# Ad8232_placa_C_malha.net
KiCad netlist of a schematic drawn in EAGLE
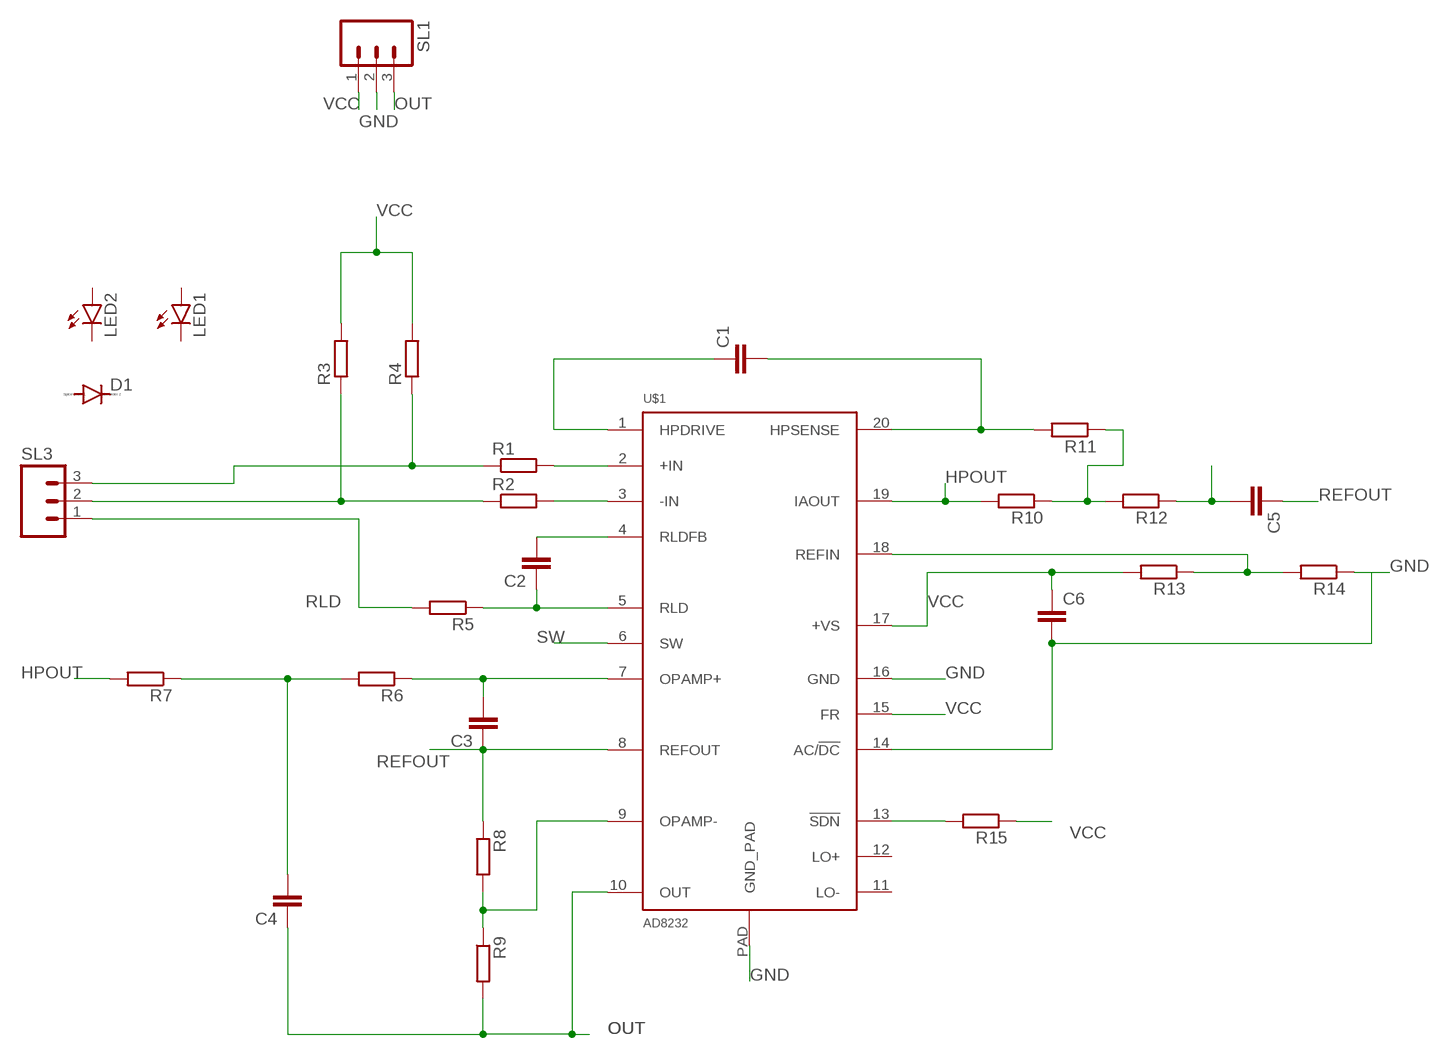
[diagram p0: schematic, sheet 1]

(export (version "E")
  (design (tool "Eeschema 10.0.6"))
  (components
    (comp (ref "C1")
      (value "C-EUC0805")
      (footprint "eagle-import:C0805")
      (libsource (lib "eagle-import") (part "C-EUC0805"))
    )
    (comp (ref "C2")
      (value "C-EUC0805")
      (footprint "eagle-import:C0805")
      (libsource (lib "eagle-import") (part "C-EUC0805"))
    )
    (comp (ref "C3")
      (value "C-EUC0805")
      (footprint "eagle-import:C0805")
      (libsource (lib "eagle-import") (part "C-EUC0805"))
    )
    (comp (ref "C4")
      (value "C-EUC0805")
      (footprint "eagle-import:C0805")
      (libsource (lib "eagle-import") (part "C-EUC0805"))
    )
    (comp (ref "C5")
      (value "C-EUC0805")
      (footprint "eagle-import:C0805")
      (libsource (lib "eagle-import") (part "C-EUC0805"))
    )
    (comp (ref "C6")
      (value "C-EUC0805")
      (footprint "eagle-import:C0805")
      (libsource (lib "eagle-import") (part "C-EUC0805"))
    )
    (comp (ref "D1")
      (value "DIODE-MINIMELF")
      (footprint "eagle-import:MINIMELF")
      (libsource (lib "eagle-import") (part "DIODE-MINIMELF"))
    )
    (comp (ref "LED1")
      (value "LEDCHIPLED_0603")
      (footprint "eagle-import:CHIPLED_0603")
      (libsource (lib "eagle-import") (part "LEDCHIPLED_0603"))
    )
    (comp (ref "LED2")
      (value "LEDCHIPLED_0603")
      (footprint "eagle-import:CHIPLED_0603")
      (libsource (lib "eagle-import") (part "LEDCHIPLED_0603"))
    )
    (comp (ref "R1")
      (value "R-EU_R0805")
      (footprint "eagle-import:R0805")
      (libsource (lib "eagle-import") (part "R-EU_R0805"))
    )
    (comp (ref "R2")
      (value "R-EU_R0805")
      (footprint "eagle-import:R0805")
      (libsource (lib "eagle-import") (part "R-EU_R0805"))
    )
    (comp (ref "R3")
      (value "R-EU_R0805")
      (footprint "eagle-import:R0805")
      (libsource (lib "eagle-import") (part "R-EU_R0805"))
    )
    (comp (ref "R4")
      (value "R-EU_R0805")
      (footprint "eagle-import:R0805")
      (libsource (lib "eagle-import") (part "R-EU_R0805"))
    )
    (comp (ref "R5")
      (value "R-EU_R0805")
      (footprint "eagle-import:R0805")
      (libsource (lib "eagle-import") (part "R-EU_R0805"))
    )
    (comp (ref "R6")
      (value "R-EU_R0805")
      (footprint "eagle-import:R0805")
      (libsource (lib "eagle-import") (part "R-EU_R0805"))
    )
    (comp (ref "R7")
      (value "R-EU_R0805")
      (footprint "eagle-import:R0805")
      (libsource (lib "eagle-import") (part "R-EU_R0805"))
    )
    (comp (ref "R8")
      (value "R-EU_R0805")
      (footprint "eagle-import:R0805")
      (libsource (lib "eagle-import") (part "R-EU_R0805"))
    )
    (comp (ref "R9")
      (value "R-EU_R0805")
      (footprint "eagle-import:R0805")
      (libsource (lib "eagle-import") (part "R-EU_R0805"))
    )
    (comp (ref "R10")
      (value "R-EU_R0805")
      (footprint "eagle-import:R0805")
      (libsource (lib "eagle-import") (part "R-EU_R0805"))
    )
    (comp (ref "R11")
      (value "R-EU_R0805")
      (footprint "eagle-import:R0805")
      (libsource (lib "eagle-import") (part "R-EU_R0805"))
    )
    (comp (ref "R12")
      (value "R-EU_R0805")
      (footprint "eagle-import:R0805")
      (libsource (lib "eagle-import") (part "R-EU_R0805"))
    )
    (comp (ref "R13")
      (value "R-EU_R0805")
      (footprint "eagle-import:R0805")
      (libsource (lib "eagle-import") (part "R-EU_R0805"))
    )
    (comp (ref "R14")
      (value "R-EU_R0805")
      (footprint "eagle-import:R0805")
      (libsource (lib "eagle-import") (part "R-EU_R0805"))
    )
    (comp (ref "R15")
      (value "R-EU_R0805")
      (footprint "eagle-import:R0805")
      (libsource (lib "eagle-import") (part "R-EU_R0805"))
    )
    (comp (ref "SL1")
      (value "M03")
      (footprint "eagle-import:03P")
      (libsource (lib "eagle-import") (part "M03"))
    )
    (comp (ref "SL3")
      (value "M03")
      (footprint "eagle-import:03P")
      (libsource (lib "eagle-import") (part "M03"))
    )
    (comp (ref "U$1")
      (value "AD8232")
      (footprint "eagle-import:LFCSP_20")
      (fields (field (name "MF") "Analog Devices"))
      (libsource (lib "eagle-import") (part "AD8232"))
    )
  )
  (nets
    (net (code "1") (name "/GND") (class "Default")
      (node (ref "C6") (pin "2") (pinfunction "2_2") (pintype "passive"))
      (node (ref "R14") (pin "1") (pinfunction "1_1") (pintype "passive"))
      (node (ref "SL1") (pin "2") (pinfunction "2_2") (pintype "passive"))
      (node (ref "U$1") (pin "14") (pinfunction "AC/~{DC}_14") (pintype "bidirectional"))
      (node (ref "U$1") (pin "16") (pinfunction "GND_16") (pintype "bidirectional"))
      (node (ref "U$1") (pin "PAD") (pinfunction "GND_PAD_PAD") (pintype "bidirectional"))
    )
    (net (code "2") (name "/HPOUT") (class "Default")
      (node (ref "R10") (pin "2") (pinfunction "2_2") (pintype "passive"))
      (node (ref "R7") (pin "2") (pinfunction "2_2") (pintype "passive"))
      (node (ref "U$1") (pin "19") (pinfunction "IAOUT_19") (pintype "bidirectional"))
    )
    (net (code "3") (name "/OUT") (class "Default")
      (node (ref "C4") (pin "1") (pinfunction "1_1") (pintype "passive"))
      (node (ref "R9") (pin "2") (pinfunction "2_2") (pintype "passive"))
      (node (ref "SL1") (pin "3") (pinfunction "3_3") (pintype "passive"))
      (node (ref "U$1") (pin "10") (pinfunction "OUT_10") (pintype "bidirectional"))
    )
    (net (code "4") (name "/REFOUT") (class "Default")
      (node (ref "C3") (pin "1") (pinfunction "1_1") (pintype "passive"))
      (node (ref "C5") (pin "1") (pinfunction "1_1") (pintype "passive"))
      (node (ref "R8") (pin "1") (pinfunction "1_1") (pintype "passive"))
      (node (ref "U$1") (pin "8") (pinfunction "REFOUT_8") (pintype "bidirectional"))
    )
    (net (code "5") (name "/RLD") (class "Default")
      (node (ref "R5") (pin "2") (pinfunction "2_2") (pintype "passive"))
      (node (ref "SL3") (pin "1") (pinfunction "1_1") (pintype "passive"))
    )
    (net (code "6") (name "/SW") (class "Default")
      (node (ref "C5") (pin "2") (pinfunction "2_2") (pintype "passive"))
      (node (ref "R12") (pin "1") (pinfunction "1_1") (pintype "passive"))
      (node (ref "U$1") (pin "6") (pinfunction "SW_6") (pintype "bidirectional"))
    )
    (net (code "7") (name "/VCC") (class "Default")
      (node (ref "C6") (pin "1") (pinfunction "1_1") (pintype "passive"))
      (node (ref "R13") (pin "2") (pinfunction "2_2") (pintype "passive"))
      (node (ref "R15") (pin "1") (pinfunction "1_1") (pintype "passive"))
      (node (ref "R3") (pin "2") (pinfunction "2_2") (pintype "passive"))
      (node (ref "R4") (pin "2") (pinfunction "2_2") (pintype "passive"))
      (node (ref "SL1") (pin "1") (pinfunction "1_1") (pintype "passive"))
      (node (ref "U$1") (pin "15") (pinfunction "FR_15") (pintype "bidirectional"))
      (node (ref "U$1") (pin "17") (pinfunction "+VS_17") (pintype "bidirectional"))
    )
    (net (code "8") (name "Net-(C4-Pad2)") (class "Default")
      (node (ref "C4") (pin "2") (pinfunction "2_2") (pintype "passive"))
      (node (ref "R6") (pin "2") (pinfunction "2_2") (pintype "passive"))
      (node (ref "R7") (pin "1") (pinfunction "1_1") (pintype "passive"))
    )
    (net (code "9") (name "Net-(R1-Pad1)") (class "Default")
      (node (ref "R1") (pin "1") (pinfunction "1_1") (pintype "passive"))
      (node (ref "R4") (pin "1") (pinfunction "1_1") (pintype "passive"))
      (node (ref "SL3") (pin "3") (pinfunction "3_3") (pintype "passive"))
    )
    (net (code "10") (name "Net-(R2-Pad1)") (class "Default")
      (node (ref "R2") (pin "1") (pinfunction "1_1") (pintype "passive"))
      (node (ref "R3") (pin "1") (pinfunction "1_1") (pintype "passive"))
      (node (ref "SL3") (pin "2") (pinfunction "2_2") (pintype "passive"))
    )
    (net (code "11") (name "Net-(R10-Pad1)") (class "Default")
      (node (ref "R10") (pin "1") (pinfunction "1_1") (pintype "passive"))
      (node (ref "R11") (pin "1") (pinfunction "1_1") (pintype "passive"))
      (node (ref "R12") (pin "2") (pinfunction "2_2") (pintype "passive"))
    )
    (net (code "12") (name "Net-(U$1-+IN)") (class "Default")
      (node (ref "R1") (pin "2") (pinfunction "2_2") (pintype "passive"))
      (node (ref "U$1") (pin "2") (pinfunction "+IN_2") (pintype "bidirectional"))
    )
    (net (code "13") (name "Net-(U$1--IN)") (class "Default")
      (node (ref "R2") (pin "2") (pinfunction "2_2") (pintype "passive"))
      (node (ref "U$1") (pin "3") (pinfunction "-IN_3") (pintype "bidirectional"))
    )
    (net (code "14") (name "Net-(U$1-HPDRIVE)") (class "Default")
      (node (ref "C1") (pin "1") (pinfunction "1_1") (pintype "passive"))
      (node (ref "U$1") (pin "1") (pinfunction "HPDRIVE_1") (pintype "bidirectional"))
    )
    (net (code "15") (name "Net-(U$1-HPSENSE)") (class "Default")
      (node (ref "C1") (pin "2") (pinfunction "2_2") (pintype "passive"))
      (node (ref "R11") (pin "2") (pinfunction "2_2") (pintype "passive"))
      (node (ref "U$1") (pin "20") (pinfunction "HPSENSE_20") (pintype "bidirectional"))
    )
    (net (code "16") (name "Net-(U$1-OPAMP+)") (class "Default")
      (node (ref "C3") (pin "2") (pinfunction "2_2") (pintype "passive"))
      (node (ref "R6") (pin "1") (pinfunction "1_1") (pintype "passive"))
      (node (ref "U$1") (pin "7") (pinfunction "OPAMP+_7") (pintype "bidirectional"))
    )
    (net (code "17") (name "Net-(U$1-OPAMP-)") (class "Default")
      (node (ref "R8") (pin "2") (pinfunction "2_2") (pintype "passive"))
      (node (ref "R9") (pin "1") (pinfunction "1_1") (pintype "passive"))
      (node (ref "U$1") (pin "9") (pinfunction "OPAMP-_9") (pintype "bidirectional"))
    )
    (net (code "18") (name "Net-(U$1-REFIN)") (class "Default")
      (node (ref "R13") (pin "1") (pinfunction "1_1") (pintype "passive"))
      (node (ref "R14") (pin "2") (pinfunction "2_2") (pintype "passive"))
      (node (ref "U$1") (pin "18") (pinfunction "REFIN_18") (pintype "bidirectional"))
    )
    (net (code "19") (name "Net-(U$1-RLD)") (class "Default")
      (node (ref "C2") (pin "1") (pinfunction "1_1") (pintype "passive"))
      (node (ref "R5") (pin "1") (pinfunction "1_1") (pintype "passive"))
      (node (ref "U$1") (pin "5") (pinfunction "RLD_5") (pintype "bidirectional"))
    )
    (net (code "20") (name "Net-(U$1-RLDFB)") (class "Default")
      (node (ref "C2") (pin "2") (pinfunction "2_2") (pintype "passive"))
      (node (ref "U$1") (pin "4") (pinfunction "RLDFB_4") (pintype "bidirectional"))
    )
    (net (code "21") (name "Net-(U$1-~{SDN})") (class "Default")
      (node (ref "R15") (pin "2") (pinfunction "2_2") (pintype "passive"))
      (node (ref "U$1") (pin "13") (pinfunction "~{SDN}_13") (pintype "bidirectional"))
    )
    (net (code "22") (name "unconnected-(D1-PadA)") (class "Default")
      (node (ref "D1") (pin "A") (pinfunction "A_A") (pintype "passive"))
    )
    (net (code "23") (name "unconnected-(D1-PadC)") (class "Default")
      (node (ref "D1") (pin "C") (pinfunction "C_C") (pintype "passive"))
    )
    (net (code "24") (name "unconnected-(LED1-PadA)") (class "Default")
      (node (ref "LED1") (pin "A") (pinfunction "A_A") (pintype "passive"))
    )
    (net (code "25") (name "unconnected-(LED1-PadC)") (class "Default")
      (node (ref "LED1") (pin "C") (pinfunction "C_C") (pintype "passive"))
    )
    (net (code "26") (name "unconnected-(LED2-PadA)") (class "Default")
      (node (ref "LED2") (pin "A") (pinfunction "A_A") (pintype "passive"))
    )
    (net (code "27") (name "unconnected-(LED2-PadC)") (class "Default")
      (node (ref "LED2") (pin "C") (pinfunction "C_C") (pintype "passive"))
    )
    (net (code "28") (name "unconnected-(U$1-LO+-Pad12)") (class "Default")
      (node (ref "U$1") (pin "12") (pinfunction "LO+_12") (pintype "bidirectional"))
    )
    (net (code "29") (name "unconnected-(U$1-LO--Pad11)") (class "Default")
      (node (ref "U$1") (pin "11") (pinfunction "LO-_11") (pintype "bidirectional"))
    )
  )
)
